# CAN.net
KiCad netlist of a schematic drawn in Altium Designer
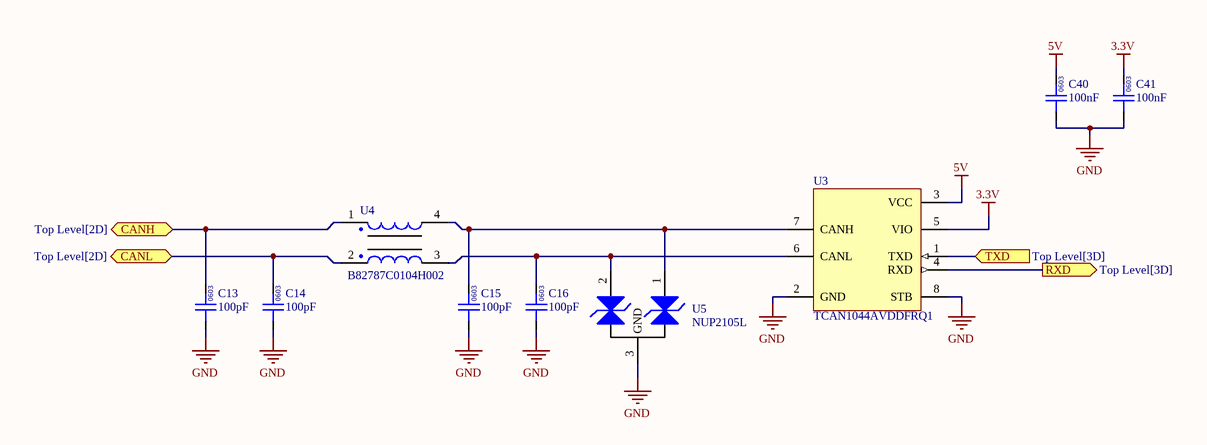
[diagram p0: CAN.SchDoc]

(export (version "E")
  (design (tool "Eeschema 10.0.6"))
  (components
    (comp (ref "C13")
      (value "100pF")
      (footprint "0603")
      (fields
        (field (name "PART NUMBER") "GRM1885C1H101JA01D")
        (field (name "MANUFACTURER") "Murata Electronics")
        (field (name "TOLERANCE") "±5%")
      )
      (libsource (lib "ts_standard_library") (part "Capacitor 0603"))
    )
    (comp (ref "C14")
      (value "100pF")
      (footprint "0603")
      (fields
        (field (name "PART NUMBER") "GRM1885C1H101JA01D")
        (field (name "MANUFACTURER") "Murata Electronics")
        (field (name "TOLERANCE") "±5%")
      )
      (libsource (lib "ts_standard_library") (part "Capacitor 0603"))
    )
    (comp (ref "C15")
      (value "100pF")
      (footprint "0603")
      (fields
        (field (name "PART NUMBER") "GRM1885C1H101JA01D")
        (field (name "MANUFACTURER") "Murata Electronics")
        (field (name "TOLERANCE") "±5%")
      )
      (libsource (lib "ts_standard_library") (part "Capacitor 0603"))
    )
    (comp (ref "C16")
      (value "100pF")
      (footprint "0603")
      (fields
        (field (name "PART NUMBER") "GRM1885C1H101JA01D")
        (field (name "MANUFACTURER") "Murata Electronics")
        (field (name "TOLERANCE") "±5%")
      )
      (libsource (lib "ts_standard_library") (part "Capacitor 0603"))
    )
    (comp (ref "C40")
      (value "100nF")
      (footprint "0603")
      (fields
        (field (name "PART NUMBER") "GCM188L81H104KA57D")
        (field (name "MANUFACTURER") "muRata")
        (field (name "TOLERANCE") "±10%")
      )
      (libsource (lib "ts_standard_library") (part "Capacitor 0603"))
    )
    (comp (ref "C41")
      (value "100nF")
      (footprint "0603")
      (fields
        (field (name "PART NUMBER") "GCM188L81H104KA57D")
        (field (name "MANUFACTURER") "muRata")
        (field (name "TOLERANCE") "±10%")
      )
      (libsource (lib "ts_standard_library") (part "Capacitor 0603"))
    )
    (comp (ref "U3")
      (value "TCAN1044AVDDFRQ1")
      (footprint "TI SOT23-8")
      (description "IC TRANSCEIVER HALF 1/1 TSOT23-8")
      (fields
        (field (name "MANUFACTURER") "Texas Instruments")
        (field (name "DIGIKEY PART NUMBER") "296-TCAN1044AVDDFRQ1CT-ND")
      )
      (libsource (lib "ts_standard_library") (part "TCAN1044AVDDFRQ1"))
    )
    (comp (ref "U4")
      (value "B82787C0104H002")
      (footprint "TDK 4-PC Pad")
      (fields
        (field (name "MANUFACTURER") "EPCOS (TDK)")
        (field (name "DIGIKEY PART NUMBER") "495-4598-1-ND")
      )
      (libsource (lib "ts_standard_library") (part "B82787C0104H002"))
    )
    (comp (ref "U5")
      (value "NUP2105L")
      (footprint "ON SOT-23")
      (description "Dual Line CAN Bus Protector")
      (fields
        (field (name "MANUFACTURER") "ON Semiconductor")
        (field (name "DIGIKEY PART NUMBER") "NUP2105LT1GOSCT-ND")
      )
      (libsource (lib "ts_standard_library") (part "NUP2105L"))
    )
  )
  (nets
    (net (code "1") (name "/CANH") (class "Default")
      (node (ref "C13") (pin "2") (pinfunction "2_2") (pintype "passive"))
      (node (ref "U4") (pin "1") (pinfunction "1_1") (pintype "passive"))
    )
    (net (code "2") (name "/CANL") (class "Default")
      (node (ref "C14") (pin "2") (pinfunction "2_2") (pintype "passive"))
      (node (ref "U4") (pin "2") (pinfunction "2_2") (pintype "passive"))
    )
    (net (code "3") (name "/RXD") (class "Default")
      (node (ref "U3") (pin "4") (pinfunction "RXD_4") (pintype "output"))
    )
    (net (code "4") (name "/TXD") (class "Default")
      (node (ref "U3") (pin "1") (pinfunction "TXD_1") (pintype "input"))
    )
    (net (code "5") (name "3.3V") (class "Default")
      (node (ref "C41") (pin "2") (pinfunction "2_2") (pintype "passive"))
      (node (ref "U3") (pin "5") (pinfunction "VIO_5") (pintype "power_in"))
    )
    (net (code "6") (name "5V") (class "Default")
      (node (ref "C40") (pin "2") (pinfunction "2_2") (pintype "passive"))
      (node (ref "U3") (pin "3") (pinfunction "VCC_3") (pintype "power_in"))
    )
    (net (code "7") (name "GND") (class "Default")
      (node (ref "C13") (pin "1") (pinfunction "1_1") (pintype "passive"))
      (node (ref "C14") (pin "1") (pinfunction "1_1") (pintype "passive"))
      (node (ref "C15") (pin "1") (pinfunction "1_1") (pintype "passive"))
      (node (ref "C16") (pin "1") (pinfunction "1_1") (pintype "passive"))
      (node (ref "C40") (pin "1") (pinfunction "1_1") (pintype "passive"))
      (node (ref "C41") (pin "1") (pinfunction "1_1") (pintype "passive"))
      (node (ref "U3") (pin "2") (pinfunction "GND_2") (pintype "power_in"))
      (node (ref "U3") (pin "8") (pinfunction "STB_8") (pintype "power_in"))
      (node (ref "U5") (pin "3") (pinfunction "GND_3") (pintype "passive"))
    )
    (net (code "8") (name "Net-(U3-CANH)") (class "Default")
      (node (ref "C15") (pin "2") (pinfunction "2_2") (pintype "passive"))
      (node (ref "U3") (pin "7") (pinfunction "CANH_7") (pintype "power_in"))
      (node (ref "U4") (pin "4") (pinfunction "4_4") (pintype "passive"))
      (node (ref "U5") (pin "1") (pinfunction "CAN_H_1") (pintype "passive"))
    )
    (net (code "9") (name "Net-(U3-CANL)") (class "Default")
      (node (ref "C16") (pin "2") (pinfunction "2_2") (pintype "passive"))
      (node (ref "U3") (pin "6") (pinfunction "CANL_6") (pintype "power_in"))
      (node (ref "U4") (pin "3") (pinfunction "3_3") (pintype "passive"))
      (node (ref "U5") (pin "2") (pinfunction "CAN_L_2") (pintype "passive"))
    )
  )
)
